# Capteurs.net
KiCad netlist of a schematic drawn in Altium Designer
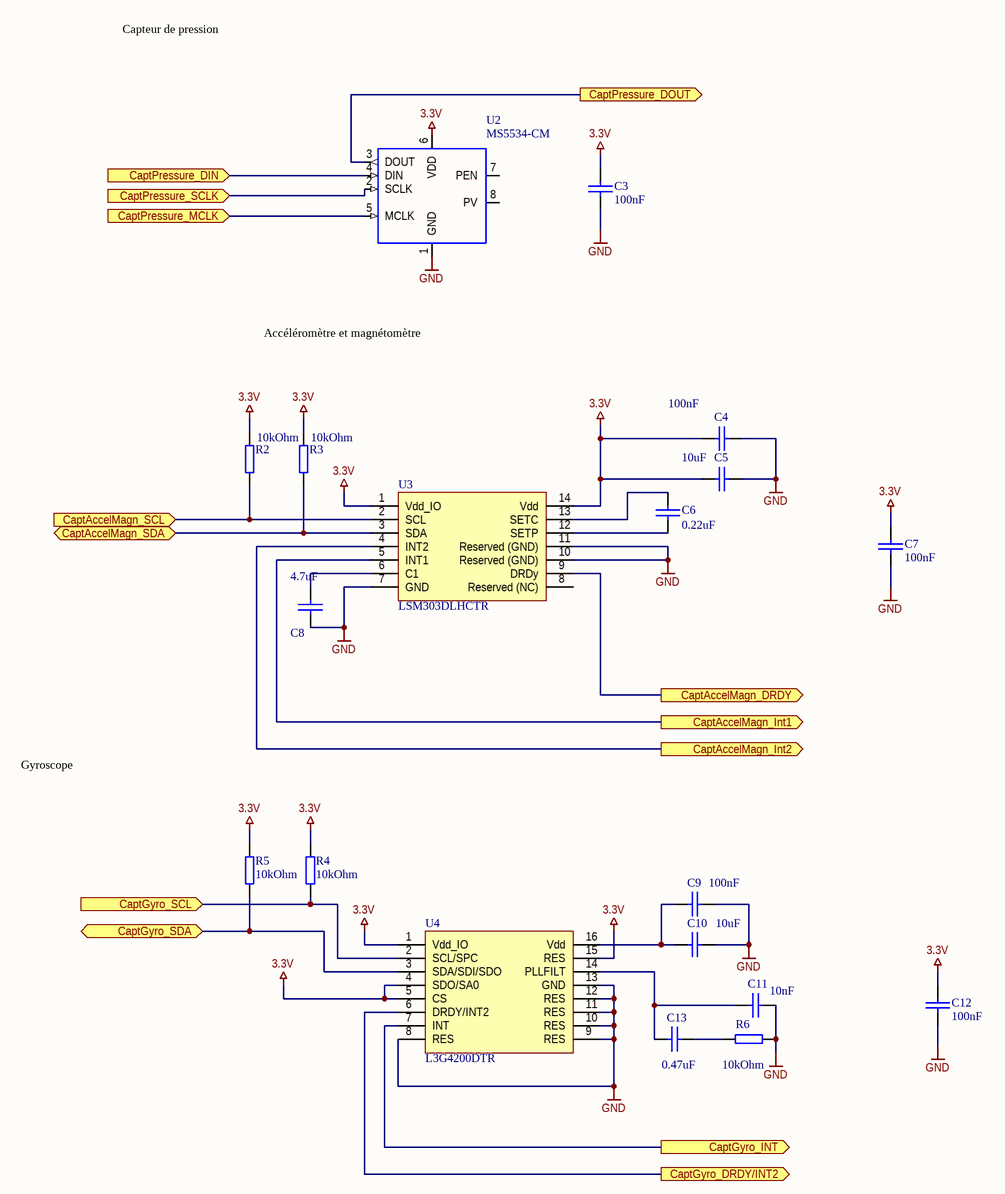
[diagram p0: Capteurs.SchDoc]

(export (version "E")
  (design (tool "Eeschema 10.0.6"))
  (components
    (comp (ref "C3")
      (value "100nF")
      (footprint "060301")
      (description "CAPA")
      (fields (field (name "Comment") "GRM188R71E104KA01D"))
      (libsource (lib "General-Sch-205") (part "CAPA"))
    )
    (comp (ref "C4")
      (value "100nF")
      (footprint "060301")
      (description "CAPA")
      (fields (field (name "Comment") "GRM188R71E104KA01D"))
      (libsource (lib "General-Sch-205") (part "CAPA"))
    )
    (comp (ref "C5")
      (value "10uF")
      (footprint "080501")
      (description "CAPA")
      (fields (field (name "Comment") "08056D106KAT2A"))
      (libsource (lib "General-Sch-205") (part "CAPA"))
    )
    (comp (ref "C6")
      (value "0.22uF")
      (footprint "120601")
      (description "CAPA")
      (fields (field (name "Comment") "UMK212F224ZD-T"))
      (libsource (lib "General-Sch-205") (part "CAPA"))
    )
    (comp (ref "C7")
      (value "100nF")
      (footprint "060301")
      (description "CAPA")
      (fields (field (name "Comment") "GRM188R71E104KA01D"))
      (libsource (lib "General-Sch-205") (part "CAPA"))
    )
    (comp (ref "C8")
      (value "4.7uF")
      (footprint "080501")
      (description "CAPA")
      (fields (field (name "Comment") "C0805C475K4PACTU"))
      (libsource (lib "General-Sch-205") (part "CAPA"))
    )
    (comp (ref "C9")
      (value "100nF")
      (footprint "060301")
      (description "CAPA")
      (fields (field (name "Comment") "GRM188R71E104KA01D"))
      (libsource (lib "General-Sch-205") (part "CAPA"))
    )
    (comp (ref "C10")
      (value "10uF")
      (footprint "080501")
      (description "CAPA")
      (fields (field (name "Comment") "08056D106KAT2A"))
      (libsource (lib "General-Sch-205") (part "CAPA"))
    )
    (comp (ref "C11")
      (value "10nF")
      (footprint "080501")
      (description "CAPA")
      (fields (field (name "Comment") "C0805C103K4RACTU"))
      (libsource (lib "General-Sch-205") (part "CAPA"))
    )
    (comp (ref "C12")
      (value "100nF")
      (footprint "060301")
      (description "CAPA")
      (fields (field (name "Comment") "GRM188R71E104KA01D"))
      (libsource (lib "General-Sch-205") (part "CAPA"))
    )
    (comp (ref "C13")
      (value "0.47uF")
      (footprint "060301")
      (description "CAPA")
      (fields (field (name "Comment") "C2012Y5V1H474Z/0.85"))
      (libsource (lib "General-Sch-205") (part "CAPA"))
    )
    (comp (ref "R2")
      (value "10kOhm")
      (footprint "080501")
      (fields (field (name "Comment") "ERJ-6GEYJ103V"))
      (libsource (lib "General-Sch-205") (part "RES"))
    )
    (comp (ref "R3")
      (value "10kOhm")
      (footprint "080501")
      (fields (field (name "Comment") "ERJ-6GEYJ103V"))
      (libsource (lib "General-Sch-205") (part "RES"))
    )
    (comp (ref "R4")
      (value "10kOhm")
      (footprint "080501")
      (fields (field (name "Comment") "ERJ-6GEYJ103V"))
      (libsource (lib "General-Sch-205") (part "RES"))
    )
    (comp (ref "R5")
      (value "10kOhm")
      (footprint "080501")
      (fields (field (name "Comment") "ERJ-6GEYJ103V"))
      (libsource (lib "General-Sch-205") (part "RES"))
    )
    (comp (ref "R6")
      (value "10kOhm")
      (footprint "080501")
      (fields (field (name "Comment") "ERJ-6GEYJ103V"))
      (libsource (lib "General-Sch-205") (part "RES"))
    )
    (comp (ref "U2")
      (value "MS5534-CM")
      (footprint "MS5534B")
      (description "Barometer Module")
      (libsource (lib "EISI") (part "MS5534B"))
    )
    (comp (ref "U3")
      (value "LSM303DLHCTR")
      (footprint "LGA-14L")
      (description "Accéléromètre et magnétomètre")
      (libsource (lib "Schlib1") (part "LSM303DLHC"))
    )
    (comp (ref "U4")
      (value "L3G4200DTR")
      (footprint "LGA-16")
      (description "Gyroscope")
      (libsource (lib "Schlib1") (part "L3G4200D"))
    )
  )
  (nets
    (net (code "1") (name "/CaptAccelMagn_DRDY") (class "Default")
      (node (ref "U3") (pin "9") (pinfunction "DRDy_9") (pintype "passive"))
    )
    (net (code "2") (name "/CaptAccelMagn_Int1") (class "Default")
      (node (ref "U3") (pin "5") (pinfunction "INT1_5") (pintype "passive"))
    )
    (net (code "3") (name "/CaptAccelMagn_Int2") (class "Default")
      (node (ref "U3") (pin "4") (pinfunction "INT2_4") (pintype "passive"))
    )
    (net (code "4") (name "/CaptAccelMagn_SCL") (class "Default")
      (node (ref "R2") (pin "1") (pintype "passive"))
      (node (ref "U3") (pin "2") (pinfunction "SCL_2") (pintype "passive"))
    )
    (net (code "5") (name "/CaptAccelMagn_SDA") (class "Default")
      (node (ref "R3") (pin "1") (pintype "passive"))
      (node (ref "U3") (pin "3") (pinfunction "SDA_3") (pintype "passive"))
    )
    (net (code "6") (name "/CaptGyro_DRDY{slash}INT2") (class "Default")
      (node (ref "U4") (pin "6") (pinfunction "DRDY/INT2_6") (pintype "passive"))
    )
    (net (code "7") (name "/CaptGyro_INT") (class "Default")
      (node (ref "U4") (pin "7") (pinfunction "INT_7") (pintype "passive"))
    )
    (net (code "8") (name "/CaptGyro_SCL") (class "Default")
      (node (ref "R4") (pin "1") (pintype "passive"))
      (node (ref "U4") (pin "2") (pinfunction "SCL/SPC_2") (pintype "passive"))
    )
    (net (code "9") (name "/CaptGyro_SDA") (class "Default")
      (node (ref "R5") (pin "1") (pintype "passive"))
      (node (ref "U4") (pin "3") (pinfunction "SDA/SDI/SDO_3") (pintype "passive"))
    )
    (net (code "10") (name "/CaptPressure_DIN") (class "Default")
      (node (ref "U2") (pin "4") (pinfunction "DIN_4") (pintype "input"))
    )
    (net (code "11") (name "/CaptPressure_DOUT") (class "Default")
      (node (ref "U2") (pin "3") (pinfunction "DOUT_3") (pintype "output"))
    )
    (net (code "12") (name "/CaptPressure_MCLK") (class "Default")
      (node (ref "U2") (pin "5") (pinfunction "MCLK_5") (pintype "input"))
    )
    (net (code "13") (name "/CaptPressure_SCLK") (class "Default")
      (node (ref "U2") (pin "2") (pinfunction "SCLK_2") (pintype "input"))
    )
    (net (code "14") (name "3.3V") (class "Default")
      (node (ref "C12") (pin "1") (pintype "passive"))
      (node (ref "C3") (pin "1") (pintype "passive"))
      (node (ref "C4") (pin "2") (pintype "passive"))
      (node (ref "C5") (pin "2") (pintype "passive"))
      (node (ref "C7") (pin "1") (pintype "passive"))
      (node (ref "R2") (pin "2") (pintype "passive"))
      (node (ref "R3") (pin "2") (pintype "passive"))
      (node (ref "R4") (pin "2") (pintype "passive"))
      (node (ref "R5") (pin "2") (pintype "passive"))
      (node (ref "U2") (pin "6") (pinfunction "VDD_6") (pintype "power_in"))
      (node (ref "U3") (pin "1") (pinfunction "Vdd_IO_1") (pintype "passive"))
      (node (ref "U3") (pin "14") (pinfunction "Vdd_14") (pintype "passive"))
      (node (ref "U4") (pin "1") (pinfunction "Vdd_IO_1") (pintype "passive"))
      (node (ref "U4") (pin "15") (pinfunction "RES_15") (pintype "passive"))
      (node (ref "U4") (pin "4") (pinfunction "SDO/SA0_4") (pintype "passive"))
      (node (ref "U4") (pin "5") (pinfunction "CS_5") (pintype "passive"))
    )
    (net (code "15") (name "GND") (class "Default")
      (node (ref "C10") (pin "1") (pintype "passive"))
      (node (ref "C11") (pin "1") (pintype "passive"))
      (node (ref "C12") (pin "2") (pintype "passive"))
      (node (ref "C3") (pin "2") (pintype "passive"))
      (node (ref "C4") (pin "1") (pintype "passive"))
      (node (ref "C5") (pin "1") (pintype "passive"))
      (node (ref "C7") (pin "2") (pintype "passive"))
      (node (ref "C8") (pin "2") (pintype "passive"))
      (node (ref "C9") (pin "1") (pintype "passive"))
      (node (ref "R6") (pin "2") (pintype "passive"))
      (node (ref "U2") (pin "1") (pinfunction "GND_1") (pintype "power_in"))
      (node (ref "U3") (pin "10") (pinfunction "Reserved_(GND)_10") (pintype "passive"))
      (node (ref "U3") (pin "11") (pinfunction "Reserved_(GND)_11") (pintype "passive"))
      (node (ref "U3") (pin "7") (pinfunction "GND_7") (pintype "passive"))
      (node (ref "U4") (pin "10") (pinfunction "RES_10") (pintype "passive"))
      (node (ref "U4") (pin "11") (pinfunction "RES_11") (pintype "passive"))
      (node (ref "U4") (pin "12") (pinfunction "RES_12") (pintype "passive"))
      (node (ref "U4") (pin "13") (pinfunction "GND_13") (pintype "passive"))
      (node (ref "U4") (pin "8") (pinfunction "RES_8") (pintype "passive"))
      (node (ref "U4") (pin "9") (pinfunction "RES_9") (pintype "passive"))
    )
    (net (code "16") (name "Net-(C13-Pad1)") (class "Default")
      (node (ref "C13") (pin "1") (pintype "passive"))
      (node (ref "R6") (pin "1") (pintype "passive"))
    )
    (net (code "17") (name "Net-(U3-C1)") (class "Default")
      (node (ref "C8") (pin "1") (pintype "passive"))
      (node (ref "U3") (pin "6") (pinfunction "C1_6") (pintype "passive"))
    )
    (net (code "18") (name "Net-(U3-SETC)") (class "Default")
      (node (ref "C6") (pin "2") (pintype "passive"))
      (node (ref "U3") (pin "13") (pinfunction "SETC_13") (pintype "passive"))
    )
    (net (code "19") (name "Net-(U3-SETP)") (class "Default")
      (node (ref "C6") (pin "1") (pintype "passive"))
      (node (ref "U3") (pin "12") (pinfunction "SETP_12") (pintype "passive"))
    )
    (net (code "20") (name "Net-(U4-PLLFILT)") (class "Default")
      (node (ref "C11") (pin "2") (pintype "passive"))
      (node (ref "C13") (pin "2") (pintype "passive"))
      (node (ref "U4") (pin "14") (pinfunction "PLLFILT_14") (pintype "passive"))
    )
    (net (code "21") (name "Net-(U4-Vdd)") (class "Default")
      (node (ref "C10") (pin "2") (pintype "passive"))
      (node (ref "C9") (pin "2") (pintype "passive"))
      (node (ref "U4") (pin "16") (pinfunction "Vdd_16") (pintype "passive"))
    )
    (net (code "22") (name "unconnected-(U2-PEN-Pad7)") (class "Default")
      (node (ref "U2") (pin "7") (pinfunction "PEN_7") (pintype "passive"))
    )
    (net (code "23") (name "unconnected-(U2-PV-Pad8)") (class "Default")
      (node (ref "U2") (pin "8") (pinfunction "PV_8") (pintype "passive"))
    )
    (net (code "24") (name "unconnected-(U3-Reserved_(NC)-Pad8)") (class "Default")
      (node (ref "U3") (pin "8") (pinfunction "Reserved_(NC)_8") (pintype "passive"))
    )
  )
)
